# CurrentSense.net
KiCad netlist of a schematic drawn in Altium Designer
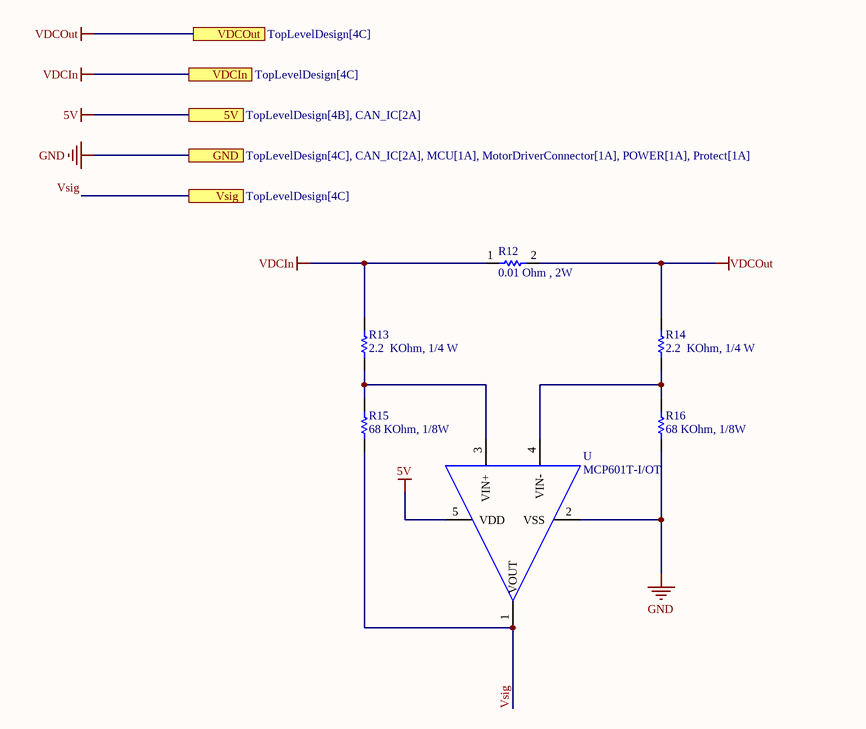
[diagram p0: CurrentSense.SchDoc]

(export (version "E")
  (design (tool "Eeschema 10.0.6"))
  (components
    (comp (ref "R12")
      (value "0.01 Ohm , 2W")
      (footprint "FP-WSLP2512R0100FEA-IPC_A")
      (description "RES 0.01 OHM 1% 3W 2512")
      (fields (field (name "TOLERANCE") "1%"))
      (libsource (lib "Tin Tran") (part "CMP-02407-010954-1"))
    )
    (comp (ref "R13")
      (value "2.2  KOhm, 1/4 W")
      (footprint "resistor_0603")
      (description "RES, size 0603, 2.2  KOhm, 1/4 W")
      (fields (field (name "Comment") "0006032221"))
      (libsource (lib "Tin Tran") (part "00060371541"))
    )
    (comp (ref "R14")
      (value "2.2  KOhm, 1/4 W")
      (footprint "resistor_0603")
      (description "RES, size 0603, 2.2  KOhm, 1/4 W")
      (fields (field (name "Comment") "0006032221"))
      (libsource (lib "Tin Tran") (part "00060371541"))
    )
    (comp (ref "R15")
      (value "68 KOhm, 1/8W")
      (footprint "RESISTOR_0805")
      (description "RES, size 0805, 68 KOhm, 1/8W")
      (fields (field (name "Comment") "0008056835"))
      (libsource (lib "Tin Tran") (part "0008052035_1"))
    )
    (comp (ref "R16")
      (value "68 KOhm, 1/8W")
      (footprint "RESISTOR_0805")
      (description "RES, size 0805, 68 KOhm, 1/8W")
      (fields (field (name "Comment") "0008056835"))
      (libsource (lib "Tin Tran") (part "0008052035_1"))
    )
    (comp (ref "U")
      (value "MCP601T-I/OT")
      (footprint "SOT95P280X145-5N")
      (description "General Purpose Amplifier 1 Circuit Rail-to-Rail SOT-23-5")
      (fields (field (name "MF") "Microchip"))
      (libsource (lib "Tin Tran") (part "MCP601T-I/OT"))
    )
  )
  (nets
    (net (code "1") (name "/Vsig") (class "Default")
      (node (ref "R15") (pin "1") (pinfunction "1_1") (pintype "passive"))
      (node (ref "U") (pin "1") (pinfunction "VOUT_1") (pintype "passive"))
    )
    (net (code "2") (name "5V") (class "Default")
      (node (ref "U") (pin "5") (pinfunction "VDD_5") (pintype "passive"))
    )
    (net (code "3") (name "GND") (class "Default")
      (node (ref "R16") (pin "1") (pinfunction "1_1") (pintype "passive"))
      (node (ref "U") (pin "2") (pinfunction "VSS_2") (pintype "passive"))
    )
    (net (code "4") (name "Net-(U-VIN+)") (class "Default")
      (node (ref "R13") (pin "1") (pinfunction "1_1") (pintype "passive"))
      (node (ref "R15") (pin "2") (pinfunction "2_2") (pintype "passive"))
      (node (ref "U") (pin "3") (pinfunction "VIN+_3") (pintype "passive"))
    )
    (net (code "5") (name "Net-(U-VIN-)") (class "Default")
      (node (ref "R14") (pin "1") (pinfunction "1_1") (pintype "passive"))
      (node (ref "R16") (pin "2") (pinfunction "2_2") (pintype "passive"))
      (node (ref "U") (pin "4") (pinfunction "VIN-_4") (pintype "passive"))
    )
    (net (code "6") (name "VDCIn") (class "Default")
      (node (ref "R12") (pin "1") (pinfunction "1_1") (pintype "passive"))
      (node (ref "R13") (pin "2") (pinfunction "2_2") (pintype "passive"))
    )
    (net (code "7") (name "VDCOut") (class "Default")
      (node (ref "R12") (pin "2") (pinfunction "2_2") (pintype "passive"))
      (node (ref "R14") (pin "2") (pinfunction "2_2") (pintype "passive"))
    )
  )
)
